# MB1046.net
KiCad netlist of a schematic drawn in Altium Designer
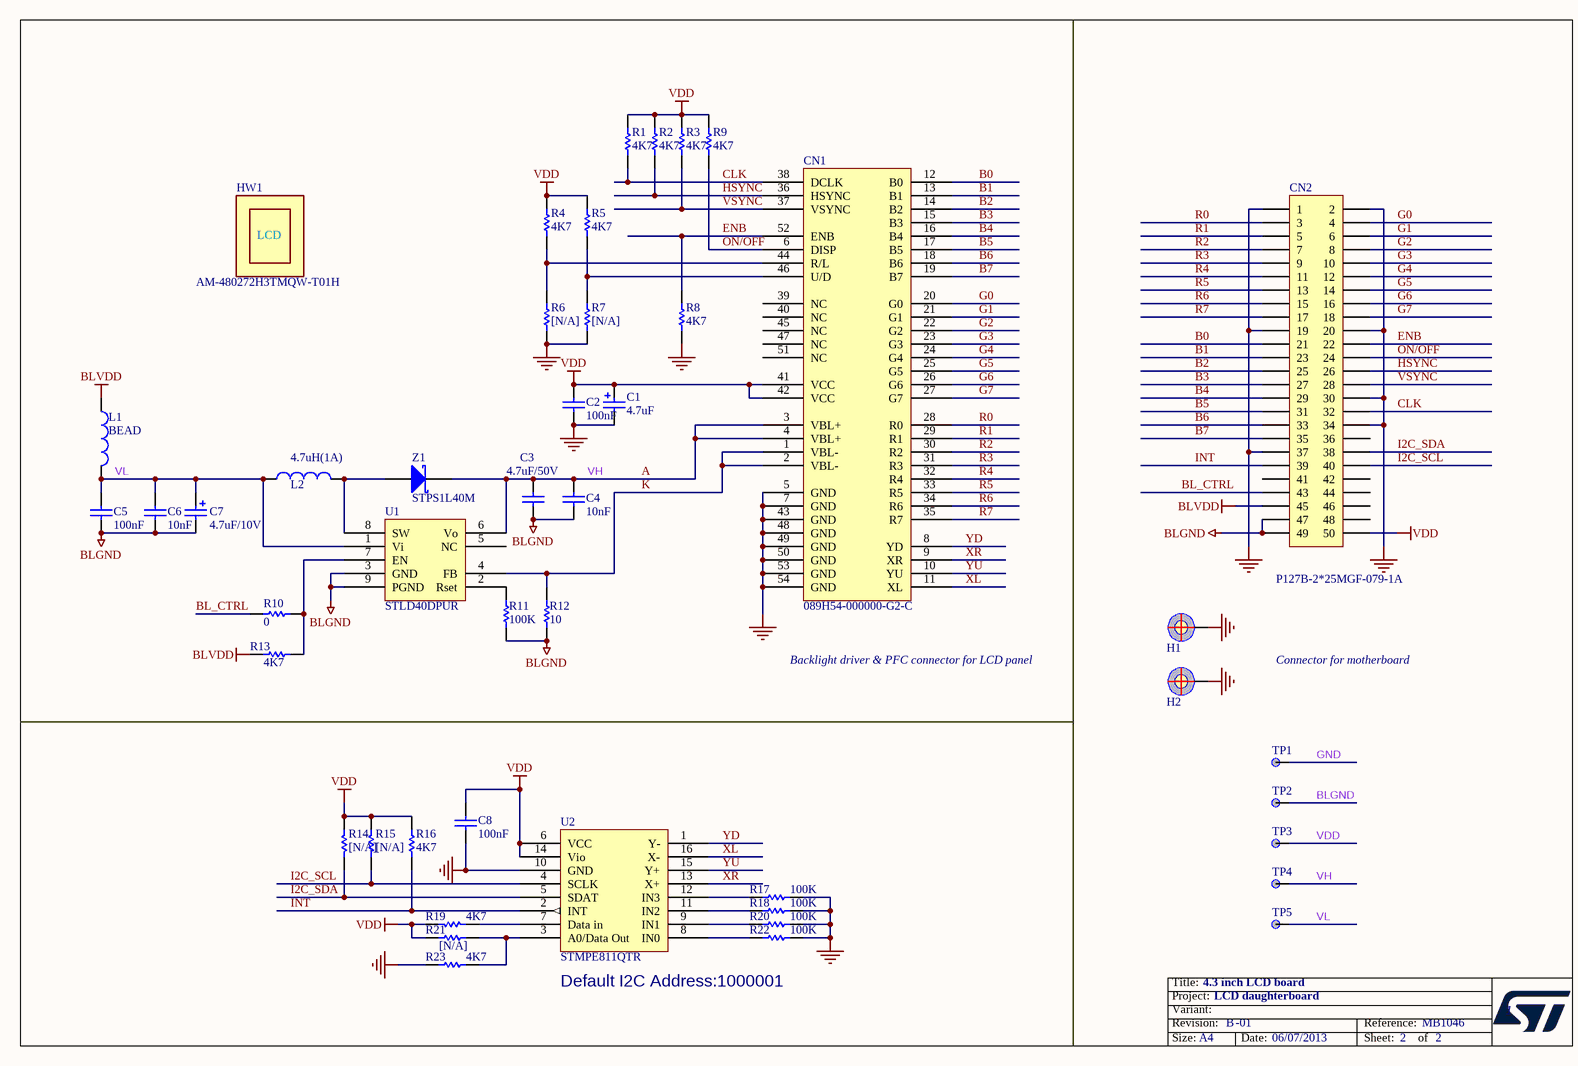
[diagram p0: MB1046.SchDoc]

(export (version "E")
  (design (tool "Eeschema 10.0.6"))
  (components
    (comp (ref "C1")
      (value "4.7uF")
      (footprint "TAN-A")
      (description "Polarized Capacitor (Radial)")
      (fields (field (name "PUBLISHER") "Altium Limited"))
      (libsource (lib "Miscellaneous Devices") (part "Cap Pol1"))
    )
    (comp (ref "C2")
      (value "100nF")
      (footprint "0603C")
      (description "Capacitor")
      (fields (field (name "PUBLISHER") "Altium Limited"))
      (libsource (lib "Miscellaneous Devices") (part "CAP"))
    )
    (comp (ref "C3")
      (value "4.7uF/50V")
      (footprint "1206C")
      (description "Capacitor")
      (fields (field (name "PUBLISHER") "Altium Limited"))
      (libsource (lib "Miscellaneous Devices") (part "CAP"))
    )
    (comp (ref "C4")
      (value "10nF")
      (footprint "0603C")
      (description "Capacitor")
      (fields (field (name "PUBLISHER") "Altium Limited"))
      (libsource (lib "*") (part "CAP"))
    )
    (comp (ref "C5")
      (value "100nF")
      (footprint "0603C")
      (description "Capacitor")
      (fields (field (name "PUBLISHER") "Altium Limited"))
      (libsource (lib "Miscellaneous Devices") (part "CAP"))
    )
    (comp (ref "C6")
      (value "10nF")
      (footprint "0603C")
      (description "Capacitor")
      (fields (field (name "PUBLISHER") "Altium Limited"))
      (libsource (lib "Miscellaneous Devices") (part "CAP"))
    )
    (comp (ref "C7")
      (value "4.7uF/10V")
      (footprint "1206C")
      (description "Polarized Capacitor (Radial)")
      (fields (field (name "PUBLISHER") "Altium Limited"))
      (libsource (lib "Miscellaneous Devices") (part "Cap Pol1"))
    )
    (comp (ref "C8")
      (value "100nF")
      (footprint "0603C")
      (description "Capacitor")
      (fields (field (name "PUBLISHER") "Altium Limited"))
      (libsource (lib "Miscellaneous Devices") (part "CAP"))
    )
    (comp (ref "CN1")
      (value "089H54-000000-G2-C")
      (footprint "FPC54_0R5_089H54_LY-FPC")
      (libsource (lib "MB1046") (part "089H54-000000-G2-C"))
    )
    (comp (ref "CN2")
      (value "P127B-2*25MGF-079-1A")
      (footprint "FTSH-125-01-F-DV")
      (description "Header, 26-Pin, Dual row")
      (fields (field (name "PUBLISHER") "Altium Limited"))
      (libsource (lib "mb1045") (part "Header 25X2"))
    )
    (comp (ref "H1")
      (value "POSITION HOLE")
      (footprint "HOLE_C9D4R5")
      (libsource (lib "mb1045") (part "POSITION HOLE"))
    )
    (comp (ref "H2")
      (value "POSITION HOLE")
      (footprint "HOLE_C9D4R5")
      (libsource (lib "mb1045") (part "POSITION HOLE"))
    )
    (comp (ref "HW1") (value "AM-480272H3TMQW-T01H") (libsource (lib "MB1046") (part "LCD_MODULE")))
    (comp (ref "L1")
      (value "BEAD")
      (footprint "0603L")
      (description "Inductor")
      (fields (field (name "PUBLISHER") "Altium Limited"))
      (libsource (lib "Miscellaneous Devices") (part "Inductor"))
    )
    (comp (ref "L2")
      (value "4.7uH(1A)")
      (footprint "1210L")
      (description "Inductor")
      (fields (field (name "PUBLISHER") "Altium Limited"))
      (libsource (lib "Miscellaneous Devices") (part "Inductor"))
    )
    (comp (ref "R1")
      (value "4K7")
      (footprint "0603R")
      (description "Resistor")
      (fields (field (name "PUBLISHER") "Altium Limited"))
      (libsource (lib "*") (part "Res1"))
    )
    (comp (ref "R2")
      (value "4K7")
      (footprint "0603R")
      (description "Resistor")
      (fields (field (name "PUBLISHER") "Altium Limited"))
      (libsource (lib "*") (part "Res1"))
    )
    (comp (ref "R3")
      (value "4K7")
      (footprint "0603R")
      (description "Resistor")
      (fields (field (name "PUBLISHER") "Altium Limited"))
      (libsource (lib "*") (part "Res1"))
    )
    (comp (ref "R4")
      (value "4K7")
      (footprint "0603R")
      (description "Resistor")
      (fields (field (name "PUBLISHER") "Altium Limited"))
      (libsource (lib "*") (part "Res1"))
    )
    (comp (ref "R5")
      (value "4K7")
      (footprint "0603R")
      (description "Resistor")
      (fields (field (name "PUBLISHER") "Altium Limited"))
      (libsource (lib "*") (part "Res1"))
    )
    (comp (ref "R6")
      (value "[N/A]")
      (footprint "0603R")
      (description "Resistor")
      (fields (field (name "PUBLISHER") "Altium Limited"))
      (libsource (lib "*") (part "Res1"))
    )
    (comp (ref "R7")
      (value "[N/A]")
      (footprint "0603R")
      (description "Resistor")
      (fields (field (name "PUBLISHER") "Altium Limited"))
      (libsource (lib "*") (part "Res1"))
    )
    (comp (ref "R8")
      (value "4K7")
      (footprint "0603R")
      (description "Resistor")
      (fields (field (name "PUBLISHER") "Altium Limited"))
      (libsource (lib "*") (part "Res1"))
    )
    (comp (ref "R9")
      (value "4K7")
      (footprint "0603R")
      (description "Resistor")
      (fields (field (name "PUBLISHER") "Altium Limited"))
      (libsource (lib "*") (part "Res1"))
    )
    (comp (ref "R10")
      (value "0")
      (footprint "0603R")
      (description "Resistor")
      (fields (field (name "PUBLISHER") "Altium Limited"))
      (libsource (lib "Miscellaneous Devices") (part "Res1"))
    )
    (comp (ref "R11")
      (value "100K")
      (footprint "0603R")
      (description "Resistor")
      (fields (field (name "PUBLISHER") "Altium Limited"))
      (libsource (lib "Miscellaneous Devices") (part "Res1"))
    )
    (comp (ref "R12")
      (value "10")
      (footprint "0603R")
      (description "Resistor")
      (fields (field (name "PUBLISHER") "Altium Limited"))
      (libsource (lib "Miscellaneous Devices") (part "Res1"))
    )
    (comp (ref "R13")
      (value "4K7")
      (footprint "0603R")
      (description "Resistor")
      (fields (field (name "PUBLISHER") "Altium Limited"))
      (libsource (lib "Miscellaneous Devices") (part "Res1"))
    )
    (comp (ref "R14")
      (value "[N/A]")
      (footprint "0603R")
      (description "Resistor")
      (fields (field (name "PUBLISHER") "Altium Limited"))
      (libsource (lib "*") (part "Res1"))
    )
    (comp (ref "R15")
      (value "[N/A]")
      (footprint "0603R")
      (description "Resistor")
      (fields (field (name "PUBLISHER") "Altium Limited"))
      (libsource (lib "*") (part "Res1"))
    )
    (comp (ref "R16")
      (value "4K7")
      (footprint "0603R")
      (description "Resistor")
      (fields (field (name "PUBLISHER") "Altium Limited"))
      (libsource (lib "*") (part "Res1"))
    )
    (comp (ref "R17")
      (value "100K")
      (footprint "0603R")
      (description "Resistor")
      (fields (field (name "PUBLISHER") "Altium Limited"))
      (libsource (lib "MB915_1") (part "res1"))
    )
    (comp (ref "R18")
      (value "100K")
      (footprint "0603R")
      (description "Resistor")
      (fields (field (name "PUBLISHER") "Altium Limited"))
      (libsource (lib "MB915_1") (part "res1"))
    )
    (comp (ref "R19")
      (value "4K7")
      (footprint "0603R")
      (description "Resistor")
      (fields (field (name "PUBLISHER") "Altium Limited"))
      (libsource (lib "") (part "Res1_1"))
    )
    (comp (ref "R20")
      (value "100K")
      (footprint "0603R")
      (description "Resistor")
      (fields (field (name "PUBLISHER") "Altium Limited"))
      (libsource (lib "MB915_1") (part "res1"))
    )
    (comp (ref "R21")
      (value "[N/A]")
      (footprint "0603R")
      (description "Resistor")
      (fields (field (name "PUBLISHER") "Altium Limited"))
      (libsource (lib "Miscellaneous Devices") (part "Res1"))
    )
    (comp (ref "R22")
      (value "100K")
      (footprint "0603R")
      (description "Resistor")
      (fields (field (name "PUBLISHER") "Altium Limited"))
      (libsource (lib "MB915_1") (part "res1"))
    )
    (comp (ref "R23")
      (value "4K7")
      (footprint "0603R")
      (description "Resistor")
      (fields (field (name "PUBLISHER") "Altium Limited"))
      (libsource (lib "*") (part "Res1"))
    )
    (comp (ref "TP1") (value "~") (footprint "TP") (libsource (lib "*") (part "TP")))
    (comp (ref "TP2") (value "~") (footprint "TP") (libsource (lib "*") (part "TP")))
    (comp (ref "TP3") (value "~") (footprint "TP") (libsource (lib "*") (part "TP")))
    (comp (ref "TP4") (value "~") (footprint "TP") (libsource (lib "*") (part "TP")))
    (comp (ref "TP5") (value "~") (footprint "TP") (libsource (lib "*") (part "TP")))
    (comp (ref "U1")
      (value "STLD40DPUR")
      (footprint "SON8_0R65_3X3")
      (libsource (lib "3.2LCD_daughterboard") (part "STLD40DPMR"))
    )
    (comp (ref "U2")
      (value "STMPE811QTR")
      (footprint "QFN16_0R5_3X3")
      (libsource (lib "MB784") (part "STMPE811"))
    )
    (comp (ref "Z1")
      (value "STPS1L40M")
      (footprint "DO-216AA")
      (description "Schottky Diode")
      (fields (field (name "PUBLISHER") "Altium Limited"))
      (libsource (lib "Miscellaneous Devices") (part "D Schottky"))
    )
  )
  (nets
    (net (code "1") (name "/A") (class "Default")
      (node (ref "C3") (pin "1") (pinfunction "1_1") (pintype "passive"))
      (node (ref "C4") (pin "2") (pinfunction "2_2") (pintype "passive"))
      (node (ref "CN1") (pin "3") (pinfunction "VBL+_3") (pintype "passive"))
      (node (ref "CN1") (pin "4") (pinfunction "VBL+_4") (pintype "passive"))
      (node (ref "TP4") (pin "1") (pinfunction "1_1") (pintype "passive"))
      (node (ref "U1") (pin "6") (pinfunction "Vo_6") (pintype "passive"))
      (node (ref "Z1") (pin "2") (pinfunction "K_2") (pintype "passive"))
    )
    (net (code "2") (name "/B0") (class "Default")
      (node (ref "CN1") (pin "12") (pinfunction "B0_12") (pintype "passive"))
      (node (ref "CN2") (pin "21") (pinfunction "21_21") (pintype "passive"))
    )
    (net (code "3") (name "/B1") (class "Default")
      (node (ref "CN1") (pin "13") (pinfunction "B1_13") (pintype "passive"))
      (node (ref "CN2") (pin "23") (pinfunction "23_23") (pintype "passive"))
    )
    (net (code "4") (name "/B2") (class "Default")
      (node (ref "CN1") (pin "14") (pinfunction "B2_14") (pintype "passive"))
      (node (ref "CN2") (pin "25") (pinfunction "25_25") (pintype "passive"))
    )
    (net (code "5") (name "/B3") (class "Default")
      (node (ref "CN1") (pin "15") (pinfunction "B3_15") (pintype "passive"))
      (node (ref "CN2") (pin "27") (pinfunction "27_27") (pintype "passive"))
    )
    (net (code "6") (name "/B4") (class "Default")
      (node (ref "CN1") (pin "16") (pinfunction "B4_16") (pintype "passive"))
      (node (ref "CN2") (pin "29") (pinfunction "29_29") (pintype "passive"))
    )
    (net (code "7") (name "/B5") (class "Default")
      (node (ref "CN1") (pin "17") (pinfunction "B5_17") (pintype "passive"))
      (node (ref "CN2") (pin "31") (pinfunction "31_31") (pintype "passive"))
    )
    (net (code "8") (name "/B6") (class "Default")
      (node (ref "CN1") (pin "18") (pinfunction "B6_18") (pintype "passive"))
      (node (ref "CN2") (pin "33") (pinfunction "33_33") (pintype "passive"))
    )
    (net (code "9") (name "/B7") (class "Default")
      (node (ref "CN1") (pin "19") (pinfunction "B7_19") (pintype "passive"))
      (node (ref "CN2") (pin "35") (pinfunction "35_35") (pintype "passive"))
    )
    (net (code "10") (name "/BL_CTRL") (class "Default")
      (node (ref "CN2") (pin "43") (pinfunction "43_43") (pintype "passive"))
      (node (ref "R10") (pin "2") (pinfunction "2_2") (pintype "passive"))
    )
    (net (code "11") (name "/CLK") (class "Default")
      (node (ref "CN1") (pin "38") (pinfunction "DCLK_38") (pintype "passive"))
      (node (ref "CN2") (pin "32") (pinfunction "32_32") (pintype "passive"))
      (node (ref "R1") (pin "2") (pinfunction "2_2") (pintype "passive"))
    )
    (net (code "12") (name "/ENB") (class "Default")
      (node (ref "CN1") (pin "52") (pinfunction "ENB_52") (pintype "passive"))
      (node (ref "CN2") (pin "22") (pinfunction "22_22") (pintype "passive"))
      (node (ref "R8") (pin "1") (pinfunction "1_1") (pintype "passive"))
    )
    (net (code "13") (name "/G0") (class "Default")
      (node (ref "CN1") (pin "20") (pinfunction "G0_20") (pintype "passive"))
      (node (ref "CN2") (pin "4") (pinfunction "4_4") (pintype "passive"))
    )
    (net (code "14") (name "/G1") (class "Default")
      (node (ref "CN1") (pin "21") (pinfunction "G1_21") (pintype "passive"))
      (node (ref "CN2") (pin "6") (pinfunction "6_6") (pintype "passive"))
    )
    (net (code "15") (name "/G2") (class "Default")
      (node (ref "CN1") (pin "22") (pinfunction "G2_22") (pintype "passive"))
      (node (ref "CN2") (pin "8") (pinfunction "8_8") (pintype "passive"))
    )
    (net (code "16") (name "/G3") (class "Default")
      (node (ref "CN1") (pin "23") (pinfunction "G3_23") (pintype "passive"))
      (node (ref "CN2") (pin "10") (pinfunction "10_10") (pintype "passive"))
    )
    (net (code "17") (name "/G4") (class "Default")
      (node (ref "CN1") (pin "24") (pinfunction "G4_24") (pintype "passive"))
      (node (ref "CN2") (pin "12") (pinfunction "12_12") (pintype "passive"))
    )
    (net (code "18") (name "/G5") (class "Default")
      (node (ref "CN1") (pin "25") (pinfunction "G5_25") (pintype "passive"))
      (node (ref "CN2") (pin "14") (pinfunction "14_14") (pintype "passive"))
    )
    (net (code "19") (name "/G6") (class "Default")
      (node (ref "CN1") (pin "26") (pinfunction "G6_26") (pintype "passive"))
      (node (ref "CN2") (pin "16") (pinfunction "16_16") (pintype "passive"))
    )
    (net (code "20") (name "/G7") (class "Default")
      (node (ref "CN1") (pin "27") (pinfunction "G7_27") (pintype "passive"))
      (node (ref "CN2") (pin "18") (pinfunction "18_18") (pintype "passive"))
    )
    (net (code "21") (name "/HSYNC") (class "Default")
      (node (ref "CN1") (pin "36") (pinfunction "HSYNC_36") (pintype "passive"))
      (node (ref "CN2") (pin "26") (pinfunction "26_26") (pintype "passive"))
      (node (ref "R2") (pin "2") (pinfunction "2_2") (pintype "passive"))
    )
    (net (code "22") (name "/I2C_SCL") (class "Default")
      (node (ref "CN2") (pin "40") (pinfunction "40_40") (pintype "passive"))
      (node (ref "R15") (pin "1") (pinfunction "1_1") (pintype "passive"))
      (node (ref "U2") (pin "4") (pinfunction "SCLK_4") (pintype "passive"))
    )
    (net (code "23") (name "/I2C_SDA") (class "Default")
      (node (ref "CN2") (pin "38") (pinfunction "38_38") (pintype "passive"))
      (node (ref "R14") (pin "1") (pinfunction "1_1") (pintype "passive"))
      (node (ref "U2") (pin "5") (pinfunction "SDAT_5") (pintype "passive"))
    )
    (net (code "24") (name "/INT") (class "Default")
      (node (ref "CN2") (pin "39") (pinfunction "39_39") (pintype "passive"))
      (node (ref "R16") (pin "2") (pinfunction "2_2") (pintype "passive"))
      (node (ref "U2") (pin "2") (pinfunction "INT_2") (pintype "output"))
    )
    (net (code "25") (name "/K") (class "Default")
      (node (ref "CN1") (pin "1") (pinfunction "VBL-_1") (pintype "passive"))
      (node (ref "CN1") (pin "2") (pinfunction "VBL-_2") (pintype "passive"))
      (node (ref "R12") (pin "2") (pinfunction "2_2") (pintype "passive"))
      (node (ref "U1") (pin "4") (pinfunction "FB_4") (pintype "passive"))
    )
    (net (code "26") (name "/ON{slash}OFF") (class "Default")
      (node (ref "CN1") (pin "6") (pinfunction "DISP_6") (pintype "passive"))
      (node (ref "CN2") (pin "24") (pinfunction "24_24") (pintype "passive"))
      (node (ref "R9") (pin "2") (pinfunction "2_2") (pintype "passive"))
    )
    (net (code "27") (name "/R0") (class "Default")
      (node (ref "CN1") (pin "28") (pinfunction "R0_28") (pintype "passive"))
      (node (ref "CN2") (pin "3") (pinfunction "3_3") (pintype "passive"))
    )
    (net (code "28") (name "/R1") (class "Default")
      (node (ref "CN1") (pin "29") (pinfunction "R1_29") (pintype "passive"))
      (node (ref "CN2") (pin "5") (pinfunction "5_5") (pintype "passive"))
    )
    (net (code "29") (name "/R2") (class "Default")
      (node (ref "CN1") (pin "30") (pinfunction "R2_30") (pintype "passive"))
      (node (ref "CN2") (pin "7") (pinfunction "7_7") (pintype "passive"))
    )
    (net (code "30") (name "/R3") (class "Default")
      (node (ref "CN1") (pin "31") (pinfunction "R3_31") (pintype "passive"))
      (node (ref "CN2") (pin "9") (pinfunction "9_9") (pintype "passive"))
    )
    (net (code "31") (name "/R4") (class "Default")
      (node (ref "CN1") (pin "32") (pinfunction "R4_32") (pintype "passive"))
      (node (ref "CN2") (pin "11") (pinfunction "11_11") (pintype "passive"))
    )
    (net (code "32") (name "/R5") (class "Default")
      (node (ref "CN1") (pin "33") (pinfunction "R5_33") (pintype "passive"))
      (node (ref "CN2") (pin "13") (pinfunction "13_13") (pintype "passive"))
    )
    (net (code "33") (name "/R6") (class "Default")
      (node (ref "CN1") (pin "34") (pinfunction "R6_34") (pintype "passive"))
      (node (ref "CN2") (pin "15") (pinfunction "15_15") (pintype "passive"))
    )
    (net (code "34") (name "/R7") (class "Default")
      (node (ref "CN1") (pin "35") (pinfunction "R7_35") (pintype "passive"))
      (node (ref "CN2") (pin "17") (pinfunction "17_17") (pintype "passive"))
    )
    (net (code "35") (name "/VL") (class "Default")
      (node (ref "C5") (pin "2") (pinfunction "2_2") (pintype "passive"))
      (node (ref "C6") (pin "2") (pinfunction "2_2") (pintype "passive"))
      (node (ref "C7") (pin "1") (pinfunction "1_1") (pintype "passive"))
      (node (ref "L1") (pin "2") (pinfunction "2_2") (pintype "passive"))
      (node (ref "L2") (pin "1") (pinfunction "1_1") (pintype "passive"))
      (node (ref "TP5") (pin "1") (pinfunction "1_1") (pintype "passive"))
      (node (ref "U1") (pin "1") (pinfunction "Vi_1") (pintype "passive"))
    )
    (net (code "36") (name "/VSYNC") (class "Default")
      (node (ref "CN1") (pin "37") (pinfunction "VSYNC_37") (pintype "passive"))
      (node (ref "CN2") (pin "28") (pinfunction "28_28") (pintype "passive"))
      (node (ref "R3") (pin "2") (pinfunction "2_2") (pintype "passive"))
    )
    (net (code "37") (name "/XL") (class "Default")
      (node (ref "CN1") (pin "11") (pinfunction "XL_11") (pintype "passive"))
      (node (ref "U2") (pin "16") (pinfunction "X-_16") (pintype "passive"))
    )
    (net (code "38") (name "/XR") (class "Default")
      (node (ref "CN1") (pin "9") (pinfunction "XR_9") (pintype "passive"))
      (node (ref "U2") (pin "13") (pinfunction "X+_13") (pintype "passive"))
    )
    (net (code "39") (name "/YD") (class "Default")
      (node (ref "CN1") (pin "8") (pinfunction "YD_8") (pintype "passive"))
      (node (ref "U2") (pin "1") (pinfunction "Y-_1") (pintype "passive"))
    )
    (net (code "40") (name "/YU") (class "Default")
      (node (ref "CN1") (pin "10") (pinfunction "YU_10") (pintype "passive"))
      (node (ref "U2") (pin "15") (pinfunction "Y+_15") (pintype "passive"))
    )
    (net (code "41") (name "BLGND") (class "Default")
      (node (ref "C3") (pin "2") (pinfunction "2_2") (pintype "passive"))
      (node (ref "C4") (pin "1") (pinfunction "1_1") (pintype "passive"))
      (node (ref "C5") (pin "1") (pinfunction "1_1") (pintype "passive"))
      (node (ref "C6") (pin "1") (pinfunction "1_1") (pintype "passive"))
      (node (ref "C7") (pin "2") (pinfunction "2_2") (pintype "passive"))
      (node (ref "CN2") (pin "47") (pinfunction "47_47") (pintype "passive"))
      (node (ref "CN2") (pin "49") (pinfunction "49_49") (pintype "passive"))
      (node (ref "R11") (pin "2") (pinfunction "2_2") (pintype "passive"))
      (node (ref "R12") (pin "1") (pinfunction "1_1") (pintype "passive"))
      (node (ref "TP2") (pin "1") (pinfunction "1_1") (pintype "passive"))
      (node (ref "U1") (pin "3") (pinfunction "GND_3") (pintype "passive"))
      (node (ref "U1") (pin "9") (pinfunction "PGND_9") (pintype "passive"))
    )
    (net (code "42") (name "BLVDD") (class "Default")
      (node (ref "CN2") (pin "45") (pinfunction "45_45") (pintype "passive"))
      (node (ref "L1") (pin "1") (pinfunction "1_1") (pintype "passive"))
      (node (ref "R13") (pin "2") (pinfunction "2_2") (pintype "passive"))
    )
    (net (code "43") (name "GND") (class "Default")
      (node (ref "C1") (pin "2") (pinfunction "2_2") (pintype "passive"))
      (node (ref "C2") (pin "1") (pinfunction "1_1") (pintype "passive"))
      (node (ref "C8") (pin "2") (pinfunction "2_2") (pintype "passive"))
      (node (ref "CN1") (pin "43") (pinfunction "GND_43") (pintype "passive"))
      (node (ref "CN1") (pin "48") (pinfunction "GND_48") (pintype "passive"))
      (node (ref "CN1") (pin "49") (pinfunction "GND_49") (pintype "passive"))
      (node (ref "CN1") (pin "5") (pinfunction "GND_5") (pintype "passive"))
      (node (ref "CN1") (pin "50") (pinfunction "GND_50") (pintype "passive"))
      (node (ref "CN1") (pin "53") (pinfunction "GND_53") (pintype "passive"))
      (node (ref "CN1") (pin "54") (pinfunction "GND_54") (pintype "passive"))
      (node (ref "CN1") (pin "7") (pinfunction "GND_7") (pintype "passive"))
      (node (ref "CN2") (pin "1") (pinfunction "1_1") (pintype "passive"))
      (node (ref "CN2") (pin "19") (pinfunction "19_19") (pintype "passive"))
      (node (ref "CN2") (pin "2") (pinfunction "2_2") (pintype "passive"))
      (node (ref "CN2") (pin "20") (pinfunction "20_20") (pintype "passive"))
      (node (ref "CN2") (pin "30") (pinfunction "30_30") (pintype "passive"))
      (node (ref "CN2") (pin "34") (pinfunction "34_34") (pintype "passive"))
      (node (ref "CN2") (pin "37") (pinfunction "37_37") (pintype "passive"))
      (node (ref "H1") (pin "1") (pinfunction "1_1") (pintype "passive"))
      (node (ref "H2") (pin "1") (pinfunction "1_1") (pintype "passive"))
      (node (ref "R17") (pin "1") (pinfunction "1_1") (pintype "passive"))
      (node (ref "R18") (pin "1") (pinfunction "1_1") (pintype "passive"))
      (node (ref "R20") (pin "1") (pinfunction "1_1") (pintype "passive"))
      (node (ref "R22") (pin "1") (pinfunction "1_1") (pintype "passive"))
      (node (ref "R23") (pin "1") (pinfunction "1_1") (pintype "passive"))
      (node (ref "R6") (pin "2") (pinfunction "2_2") (pintype "passive"))
      (node (ref "R7") (pin "2") (pinfunction "2_2") (pintype "passive"))
      (node (ref "R8") (pin "2") (pinfunction "2_2") (pintype "passive"))
      (node (ref "TP1") (pin "1") (pinfunction "1_1") (pintype "passive"))
      (node (ref "U2") (pin "10") (pinfunction "GND_10") (pintype "passive"))
    )
    (net (code "44") (name "Net-(CN1-R{slash}L)") (class "Default")
      (node (ref "CN1") (pin "44") (pinfunction "R/L_44") (pintype "passive"))
      (node (ref "R4") (pin "2") (pinfunction "2_2") (pintype "passive"))
      (node (ref "R6") (pin "1") (pinfunction "1_1") (pintype "passive"))
    )
    (net (code "45") (name "Net-(CN1-U{slash}D)") (class "Default")
      (node (ref "CN1") (pin "46") (pinfunction "U/D_46") (pintype "passive"))
      (node (ref "R5") (pin "2") (pinfunction "2_2") (pintype "passive"))
      (node (ref "R7") (pin "1") (pinfunction "1_1") (pintype "passive"))
    )
    (net (code "46") (name "Net-(U1-EN)") (class "Default")
      (node (ref "R10") (pin "1") (pinfunction "1_1") (pintype "passive"))
      (node (ref "R13") (pin "1") (pinfunction "1_1") (pintype "passive"))
      (node (ref "U1") (pin "7") (pinfunction "EN_7") (pintype "passive"))
    )
    (net (code "47") (name "Net-(U1-Rset)") (class "Default")
      (node (ref "R11") (pin "1") (pinfunction "1_1") (pintype "passive"))
      (node (ref "U1") (pin "2") (pinfunction "Rset_2") (pintype "passive"))
    )
    (net (code "48") (name "Net-(U1-SW)") (class "Default")
      (node (ref "L2") (pin "2") (pinfunction "2_2") (pintype "passive"))
      (node (ref "U1") (pin "8") (pinfunction "SW_8") (pintype "passive"))
      (node (ref "Z1") (pin "1") (pinfunction "A_1") (pintype "passive"))
    )
    (net (code "49") (name "Net-(U2-A0{slash}Data_Out)") (class "Default")
      (node (ref "R21") (pin "1") (pinfunction "1_1") (pintype "passive"))
      (node (ref "R23") (pin "2") (pinfunction "2_2") (pintype "passive"))
      (node (ref "U2") (pin "3") (pinfunction "A0/Data_Out_3") (pintype "passive"))
    )
    (net (code "50") (name "Net-(U2-Data_in)") (class "Default")
      (node (ref "R19") (pin "1") (pinfunction "1_1") (pintype "passive"))
      (node (ref "U2") (pin "7") (pinfunction "Data_in_7") (pintype "passive"))
    )
    (net (code "51") (name "Net-(U2-IN0)") (class "Default")
      (node (ref "R22") (pin "2") (pinfunction "2_2") (pintype "passive"))
      (node (ref "U2") (pin "8") (pinfunction "IN0_8") (pintype "passive"))
    )
    (net (code "52") (name "Net-(U2-IN1)") (class "Default")
      (node (ref "R20") (pin "2") (pinfunction "2_2") (pintype "passive"))
      (node (ref "U2") (pin "9") (pinfunction "IN1_9") (pintype "passive"))
    )
    (net (code "53") (name "Net-(U2-IN2)") (class "Default")
      (node (ref "R18") (pin "2") (pinfunction "2_2") (pintype "passive"))
      (node (ref "U2") (pin "11") (pinfunction "IN2_11") (pintype "passive"))
    )
    (net (code "54") (name "Net-(U2-IN3)") (class "Default")
      (node (ref "R17") (pin "2") (pinfunction "2_2") (pintype "passive"))
      (node (ref "U2") (pin "12") (pinfunction "IN3_12") (pintype "passive"))
    )
    (net (code "55") (name "VDD") (class "Default")
      (node (ref "C1") (pin "1") (pinfunction "1_1") (pintype "passive"))
      (node (ref "C2") (pin "2") (pinfunction "2_2") (pintype "passive"))
      (node (ref "C8") (pin "1") (pinfunction "1_1") (pintype "passive"))
      (node (ref "CN1") (pin "41") (pinfunction "VCC_41") (pintype "passive"))
      (node (ref "CN1") (pin "42") (pinfunction "VCC_42") (pintype "passive"))
      (node (ref "CN2") (pin "50") (pinfunction "50_50") (pintype "passive"))
      (node (ref "R1") (pin "1") (pinfunction "1_1") (pintype "passive"))
      (node (ref "R14") (pin "2") (pinfunction "2_2") (pintype "passive"))
      (node (ref "R15") (pin "2") (pinfunction "2_2") (pintype "passive"))
      (node (ref "R16") (pin "1") (pinfunction "1_1") (pintype "passive"))
      (node (ref "R19") (pin "2") (pinfunction "2_2") (pintype "passive"))
      (node (ref "R2") (pin "1") (pinfunction "1_1") (pintype "passive"))
      (node (ref "R21") (pin "2") (pinfunction "2_2") (pintype "passive"))
      (node (ref "R3") (pin "1") (pinfunction "1_1") (pintype "passive"))
      (node (ref "R4") (pin "1") (pinfunction "1_1") (pintype "passive"))
      (node (ref "R5") (pin "1") (pinfunction "1_1") (pintype "passive"))
      (node (ref "R9") (pin "1") (pinfunction "1_1") (pintype "passive"))
      (node (ref "TP3") (pin "1") (pinfunction "1_1") (pintype "passive"))
      (node (ref "U2") (pin "14") (pinfunction "Vio_14") (pintype "passive"))
      (node (ref "U2") (pin "6") (pinfunction "VCC_6") (pintype "passive"))
    )
    (net (code "56") (name "unconnected-(CN1-NC-Pad39)") (class "Default")
      (node (ref "CN1") (pin "39") (pinfunction "NC_39") (pintype "passive"))
    )
    (net (code "57") (name "unconnected-(CN1-NC-Pad40)") (class "Default")
      (node (ref "CN1") (pin "40") (pinfunction "NC_40") (pintype "passive"))
    )
    (net (code "58") (name "unconnected-(CN1-NC-Pad45)") (class "Default")
      (node (ref "CN1") (pin "45") (pinfunction "NC_45") (pintype "passive"))
    )
    (net (code "59") (name "unconnected-(CN1-NC-Pad47)") (class "Default")
      (node (ref "CN1") (pin "47") (pinfunction "NC_47") (pintype "passive"))
    )
    (net (code "60") (name "unconnected-(CN1-NC-Pad51)") (class "Default")
      (node (ref "CN1") (pin "51") (pinfunction "NC_51") (pintype "passive"))
    )
    (net (code "61") (name "unconnected-(CN2-Pad36)") (class "Default")
      (node (ref "CN2") (pin "36") (pinfunction "36_36") (pintype "passive"))
    )
    (net (code "62") (name "unconnected-(CN2-Pad41)") (class "Default")
      (node (ref "CN2") (pin "41") (pinfunction "41_41") (pintype "passive"))
    )
    (net (code "63") (name "unconnected-(CN2-Pad42)") (class "Default")
      (node (ref "CN2") (pin "42") (pinfunction "42_42") (pintype "passive"))
    )
    (net (code "64") (name "unconnected-(CN2-Pad44)") (class "Default")
      (node (ref "CN2") (pin "44") (pinfunction "44_44") (pintype "passive"))
    )
    (net (code "65") (name "unconnected-(CN2-Pad46)") (class "Default")
      (node (ref "CN2") (pin "46") (pinfunction "46_46") (pintype "passive"))
    )
    (net (code "66") (name "unconnected-(CN2-Pad48)") (class "Default")
      (node (ref "CN2") (pin "48") (pinfunction "48_48") (pintype "passive"))
    )
    (net (code "67") (name "unconnected-(U1-NC-Pad5)") (class "Default")
      (node (ref "U1") (pin "5") (pinfunction "NC_5") (pintype "passive"))
    )
  )
)
